# hackeeg-connector-8-vertical.net
KiCad netlist of a schematic drawn in EAGLE
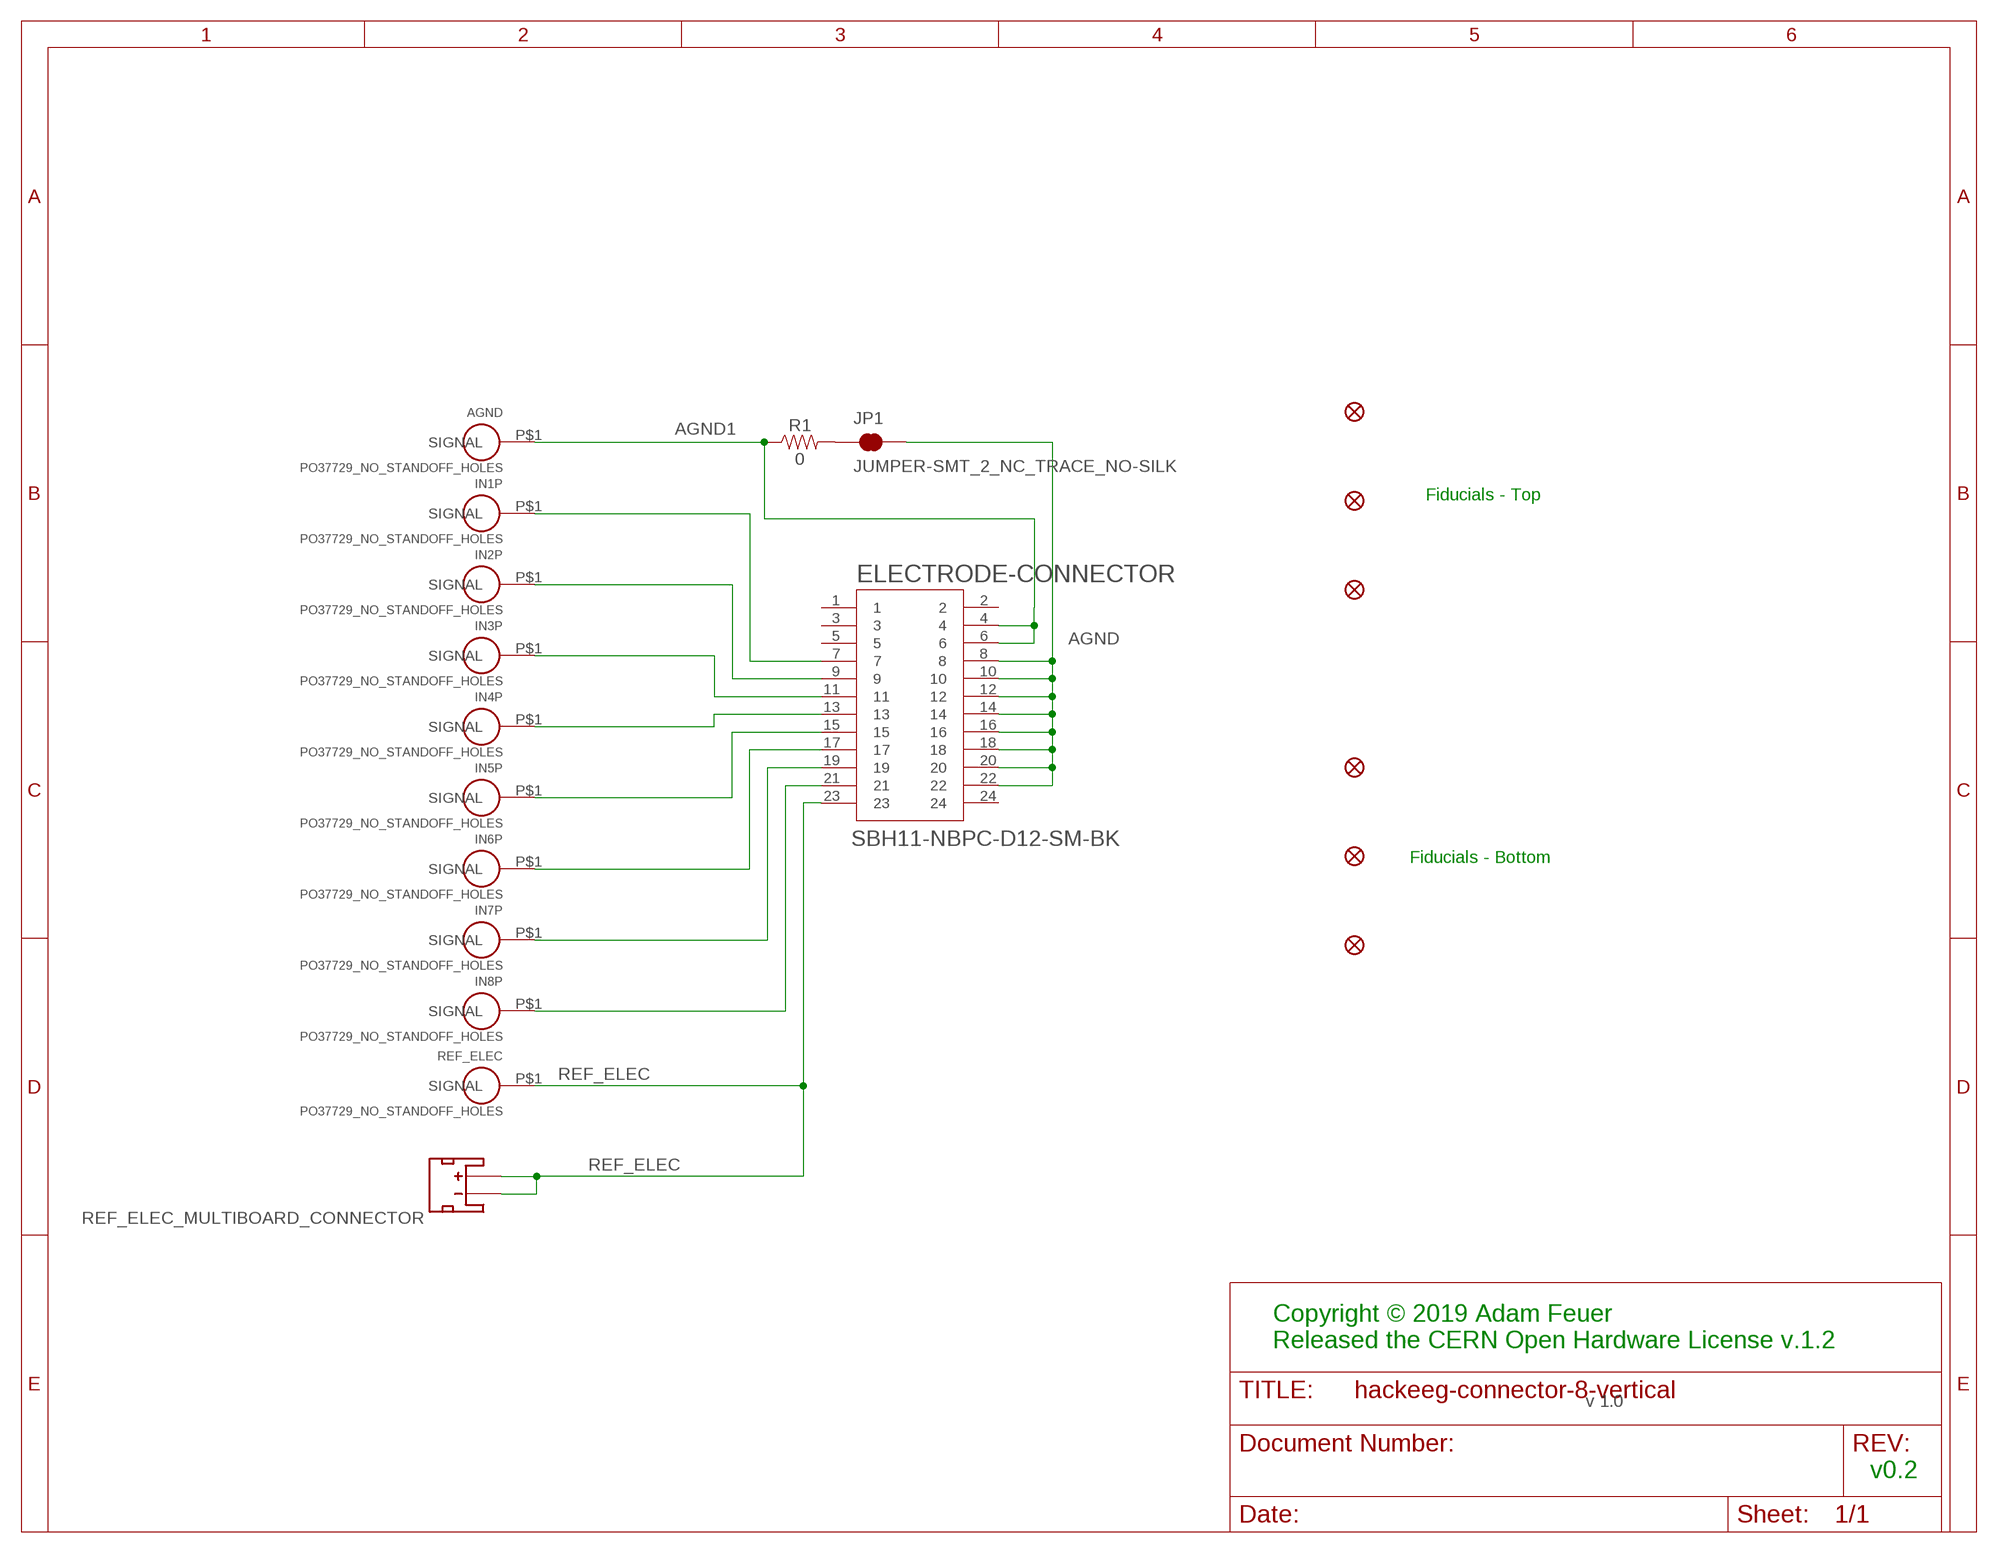
[diagram p0: schematic, sheet 1]

(export (version "E")
  (design (tool "Eeschema 10.0.6"))
  (components
    (comp (ref "AGND")
      (value "PO37729_NO_STANDOFF_HOLES")
      (footprint "eagle-import:SIMPLE0")
      (libsource (lib "eagle-import") (part "PO37729_NO_STANDOFF_HOLES"))
    )
    (comp (ref "ELECTRODE-CONNECTOR")
      (value "SBH11-NBPC-D12-SM-BK")
      (footprint "eagle-import:SULLINS_SBH11-NBPC-D12-SM-BK")
      (fields (field (name "MF") "Sullins Connector"))
      (libsource (lib "eagle-import") (part "SBH11-NBPC-D12-SM-BK"))
    )
    (comp (ref "FD1")
      (value "FIDUCIAL1X2")
      (footprint "eagle-import:FIDUCIAL-1X2")
      (libsource (lib "eagle-import") (part "FIDUCIAL1X2"))
    )
    (comp (ref "FD2")
      (value "FIDUCIAL1X2")
      (footprint "eagle-import:FIDUCIAL-1X2")
      (libsource (lib "eagle-import") (part "FIDUCIAL1X2"))
    )
    (comp (ref "FD3")
      (value "FIDUCIAL1X2")
      (footprint "eagle-import:FIDUCIAL-1X2")
      (libsource (lib "eagle-import") (part "FIDUCIAL1X2"))
    )
    (comp (ref "FD4")
      (value "FIDUCIAL1X2")
      (footprint "eagle-import:FIDUCIAL-1X2")
      (libsource (lib "eagle-import") (part "FIDUCIAL1X2"))
    )
    (comp (ref "FD5")
      (value "FIDUCIAL1X2")
      (footprint "eagle-import:FIDUCIAL-1X2")
      (libsource (lib "eagle-import") (part "FIDUCIAL1X2"))
    )
    (comp (ref "FD6")
      (value "FIDUCIAL1X2")
      (footprint "eagle-import:FIDUCIAL-1X2")
      (libsource (lib "eagle-import") (part "FIDUCIAL1X2"))
    )
    (comp (ref "IN1P")
      (value "PO37729_NO_STANDOFF_HOLES")
      (footprint "eagle-import:SIMPLE0")
      (libsource (lib "eagle-import") (part "PO37729_NO_STANDOFF_HOLES"))
    )
    (comp (ref "IN2P")
      (value "PO37729_NO_STANDOFF_HOLES")
      (footprint "eagle-import:SIMPLE0")
      (libsource (lib "eagle-import") (part "PO37729_NO_STANDOFF_HOLES"))
    )
    (comp (ref "IN3P")
      (value "PO37729_NO_STANDOFF_HOLES")
      (footprint "eagle-import:SIMPLE0")
      (libsource (lib "eagle-import") (part "PO37729_NO_STANDOFF_HOLES"))
    )
    (comp (ref "IN4P")
      (value "PO37729_NO_STANDOFF_HOLES")
      (footprint "eagle-import:SIMPLE0")
      (libsource (lib "eagle-import") (part "PO37729_NO_STANDOFF_HOLES"))
    )
    (comp (ref "IN5P")
      (value "PO37729_NO_STANDOFF_HOLES")
      (footprint "eagle-import:SIMPLE0")
      (libsource (lib "eagle-import") (part "PO37729_NO_STANDOFF_HOLES"))
    )
    (comp (ref "IN6P")
      (value "PO37729_NO_STANDOFF_HOLES")
      (footprint "eagle-import:SIMPLE0")
      (libsource (lib "eagle-import") (part "PO37729_NO_STANDOFF_HOLES"))
    )
    (comp (ref "IN7P")
      (value "PO37729_NO_STANDOFF_HOLES")
      (footprint "eagle-import:SIMPLE0")
      (libsource (lib "eagle-import") (part "PO37729_NO_STANDOFF_HOLES"))
    )
    (comp (ref "IN8P")
      (value "PO37729_NO_STANDOFF_HOLES")
      (footprint "eagle-import:SIMPLE0")
      (libsource (lib "eagle-import") (part "PO37729_NO_STANDOFF_HOLES"))
    )
    (comp (ref "JP1")
      (value "JUMPER-SMT_2_NC_TRACE_NO-SILK")
      (footprint "eagle-import:SMT-JUMPER_2_NC_TRACE_NO-SILK")
      (libsource (lib "eagle-import") (part "JUMPER-SMT_2_NC_TRACE_NO-SILK"))
    )
    (comp (ref "R1")
      (value "0")
      (footprint "eagle-import:0603")
      (libsource (lib "eagle-import") (part "0OHM-0603-1/10W-5%"))
    )
    (comp (ref "REF_ELEC")
      (value "PO37729_NO_STANDOFF_HOLES")
      (footprint "eagle-import:SIMPLE0")
      (libsource (lib "eagle-import") (part "PO37729_NO_STANDOFF_HOLES"))
    )
    (comp (ref "REF_ELEC_MULTIBOARD_CONNECTOR")
      (value "JST_2MM_MALE")
      (footprint "eagle-import:JST-2-SMD")
      (libsource (lib "eagle-import") (part "JST_2MM_MALE"))
    )
  )
  (nets
    (net (code "1") (name "/AGND") (class "Default")
      (node (ref "ELECTRODE-CONNECTOR") (pin "10") (pinfunction "10_10") (pintype "passive"))
      (node (ref "ELECTRODE-CONNECTOR") (pin "12") (pinfunction "12_12") (pintype "passive"))
      (node (ref "ELECTRODE-CONNECTOR") (pin "14") (pinfunction "14_14") (pintype "passive"))
      (node (ref "ELECTRODE-CONNECTOR") (pin "16") (pinfunction "16_16") (pintype "passive"))
      (node (ref "ELECTRODE-CONNECTOR") (pin "18") (pinfunction "18_18") (pintype "passive"))
      (node (ref "ELECTRODE-CONNECTOR") (pin "20") (pinfunction "20_20") (pintype "passive"))
      (node (ref "ELECTRODE-CONNECTOR") (pin "22") (pinfunction "22_22") (pintype "passive"))
      (node (ref "ELECTRODE-CONNECTOR") (pin "8") (pinfunction "8_8") (pintype "passive"))
      (node (ref "JP1") (pin "2") (pinfunction "2_2") (pintype "passive"))
    )
    (net (code "2") (name "/AGND1") (class "Default")
      (node (ref "AGND") (pin "P$1") (pinfunction "SIGNAL_P$1") (pintype "bidirectional"))
      (node (ref "ELECTRODE-CONNECTOR") (pin "4") (pinfunction "4_4") (pintype "passive"))
      (node (ref "ELECTRODE-CONNECTOR") (pin "6") (pinfunction "6_6") (pintype "passive"))
      (node (ref "R1") (pin "1") (pinfunction "1_1") (pintype "passive"))
    )
    (net (code "3") (name "/REF_ELEC") (class "Default")
      (node (ref "ELECTRODE-CONNECTOR") (pin "23") (pinfunction "23_23") (pintype "passive"))
      (node (ref "REF_ELEC") (pin "P$1") (pinfunction "SIGNAL_P$1") (pintype "bidirectional"))
      (node (ref "REF_ELEC_MULTIBOARD_CONNECTOR") (pin "1") (pinfunction "-_1") (pintype "bidirectional"))
      (node (ref "REF_ELEC_MULTIBOARD_CONNECTOR") (pin "2") (pinfunction "+_2") (pintype "bidirectional"))
    )
    (net (code "4") (name "Net-(IN1P-SIGNAL)") (class "Default")
      (node (ref "ELECTRODE-CONNECTOR") (pin "7") (pinfunction "7_7") (pintype "passive"))
      (node (ref "IN1P") (pin "P$1") (pinfunction "SIGNAL_P$1") (pintype "bidirectional"))
    )
    (net (code "5") (name "Net-(IN2P-SIGNAL)") (class "Default")
      (node (ref "ELECTRODE-CONNECTOR") (pin "9") (pinfunction "9_9") (pintype "passive"))
      (node (ref "IN2P") (pin "P$1") (pinfunction "SIGNAL_P$1") (pintype "bidirectional"))
    )
    (net (code "6") (name "Net-(IN3P-SIGNAL)") (class "Default")
      (node (ref "ELECTRODE-CONNECTOR") (pin "11") (pinfunction "11_11") (pintype "passive"))
      (node (ref "IN3P") (pin "P$1") (pinfunction "SIGNAL_P$1") (pintype "bidirectional"))
    )
    (net (code "7") (name "Net-(IN4P-SIGNAL)") (class "Default")
      (node (ref "ELECTRODE-CONNECTOR") (pin "13") (pinfunction "13_13") (pintype "passive"))
      (node (ref "IN4P") (pin "P$1") (pinfunction "SIGNAL_P$1") (pintype "bidirectional"))
    )
    (net (code "8") (name "Net-(IN5P-SIGNAL)") (class "Default")
      (node (ref "ELECTRODE-CONNECTOR") (pin "15") (pinfunction "15_15") (pintype "passive"))
      (node (ref "IN5P") (pin "P$1") (pinfunction "SIGNAL_P$1") (pintype "bidirectional"))
    )
    (net (code "9") (name "Net-(IN6P-SIGNAL)") (class "Default")
      (node (ref "ELECTRODE-CONNECTOR") (pin "17") (pinfunction "17_17") (pintype "passive"))
      (node (ref "IN6P") (pin "P$1") (pinfunction "SIGNAL_P$1") (pintype "bidirectional"))
    )
    (net (code "10") (name "Net-(IN7P-SIGNAL)") (class "Default")
      (node (ref "ELECTRODE-CONNECTOR") (pin "19") (pinfunction "19_19") (pintype "passive"))
      (node (ref "IN7P") (pin "P$1") (pinfunction "SIGNAL_P$1") (pintype "bidirectional"))
    )
    (net (code "11") (name "Net-(IN8P-SIGNAL)") (class "Default")
      (node (ref "ELECTRODE-CONNECTOR") (pin "21") (pinfunction "21_21") (pintype "passive"))
      (node (ref "IN8P") (pin "P$1") (pinfunction "SIGNAL_P$1") (pintype "bidirectional"))
    )
    (net (code "12") (name "Net-(JP1-Pad1)") (class "Default")
      (node (ref "JP1") (pin "1") (pinfunction "1_1") (pintype "passive"))
      (node (ref "R1") (pin "2") (pinfunction "2_2") (pintype "passive"))
    )
    (net (code "13") (name "unconnected-(ELECTRODE-CONNECTOR-Pad1)") (class "Default")
      (node (ref "ELECTRODE-CONNECTOR") (pin "1") (pinfunction "1_1") (pintype "passive"))
    )
    (net (code "14") (name "unconnected-(ELECTRODE-CONNECTOR-Pad2)") (class "Default")
      (node (ref "ELECTRODE-CONNECTOR") (pin "2") (pinfunction "2_2") (pintype "passive"))
    )
    (net (code "15") (name "unconnected-(ELECTRODE-CONNECTOR-Pad3)") (class "Default")
      (node (ref "ELECTRODE-CONNECTOR") (pin "3") (pinfunction "3_3") (pintype "passive"))
    )
    (net (code "16") (name "unconnected-(ELECTRODE-CONNECTOR-Pad5)") (class "Default")
      (node (ref "ELECTRODE-CONNECTOR") (pin "5") (pinfunction "5_5") (pintype "passive"))
    )
    (net (code "17") (name "unconnected-(ELECTRODE-CONNECTOR-Pad24)") (class "Default")
      (node (ref "ELECTRODE-CONNECTOR") (pin "24") (pinfunction "24_24") (pintype "passive"))
    )
    (net (code "18") (name "unconnected-(REF_ELEC_MULTIBOARD_CONNECTOR-PAD1-PadNC1)") (class "Default")
      (node (ref "REF_ELEC_MULTIBOARD_CONNECTOR") (pin "NC1") (pinfunction "PAD1_NC1") (pintype "bidirectional"))
    )
    (net (code "19") (name "unconnected-(REF_ELEC_MULTIBOARD_CONNECTOR-PAD2-PadNC2)") (class "Default")
      (node (ref "REF_ELEC_MULTIBOARD_CONNECTOR") (pin "NC2") (pinfunction "PAD2_NC2") (pintype "bidirectional"))
    )
  )
)
